# smc.net
KiCad netlist of a schematic drawn in EAGLE
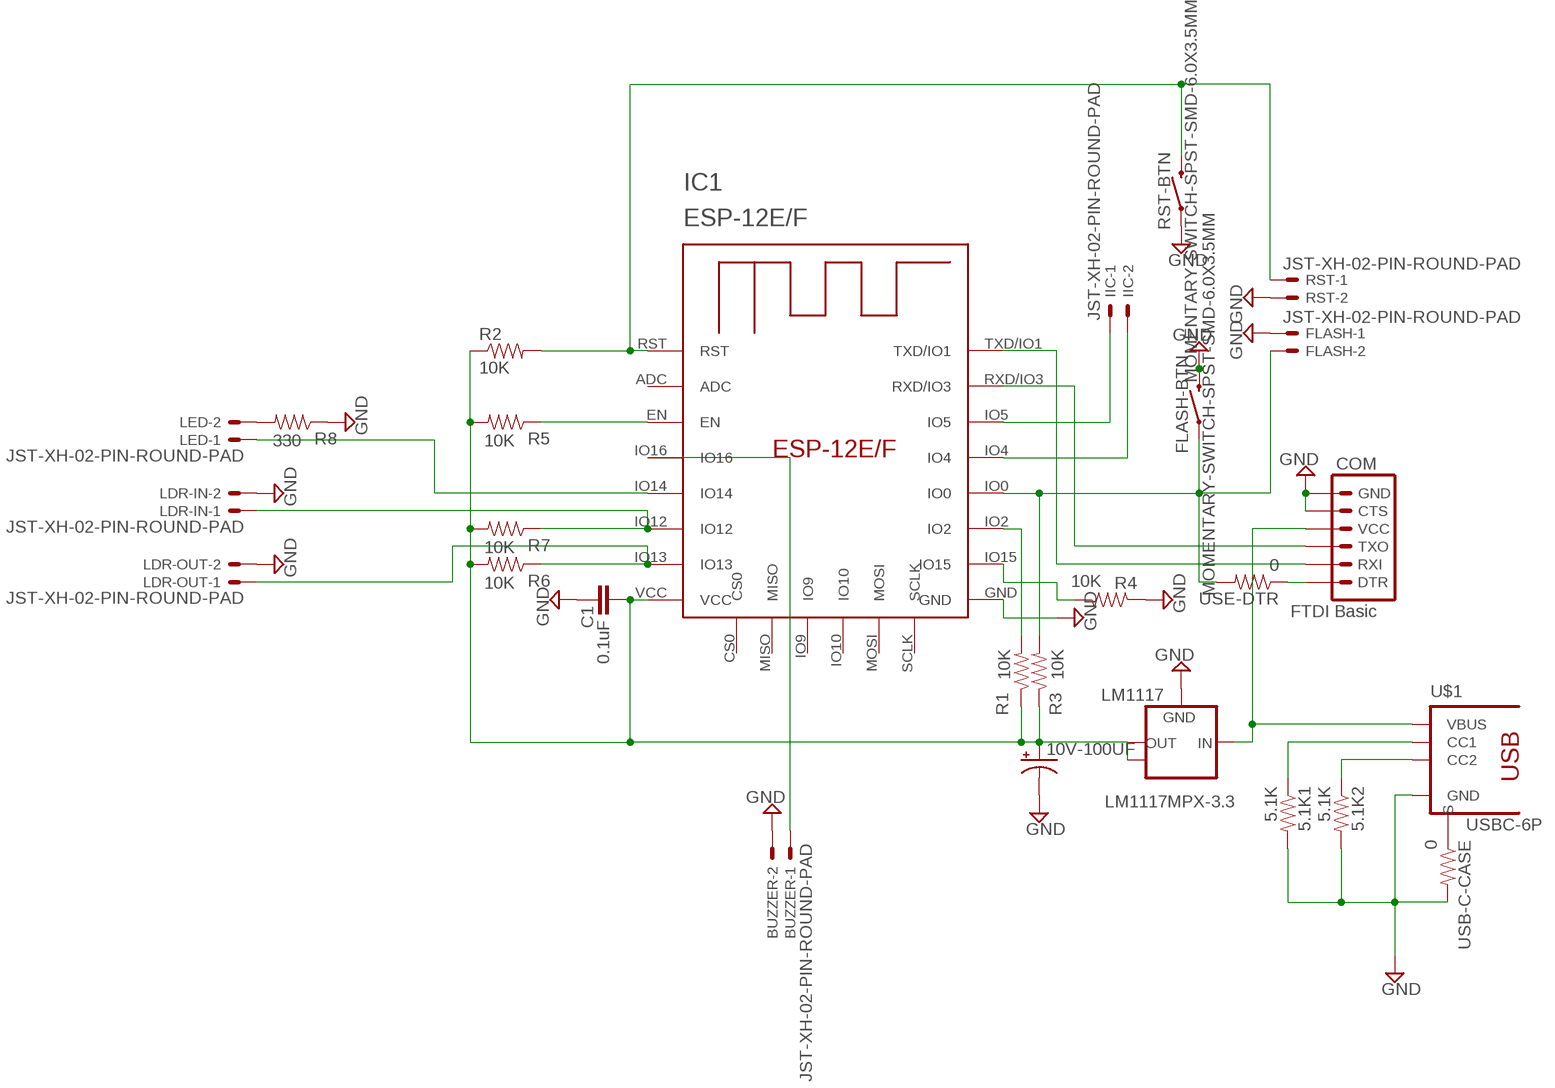
[diagram p0: schematic, sheet 1]

(export (version "E")
  (design (tool "Eeschema 10.0.6"))
  (components
    (comp (ref "5.1K1")
      (value "5.1K")
      (footprint "eagle-import:0603-RES")
      (libsource (lib "eagle-import") (part "RESISTOR0603-RES"))
    )
    (comp (ref "5.1K2")
      (value "5.1K")
      (footprint "eagle-import:0603-RES")
      (libsource (lib "eagle-import") (part "RESISTOR0603-RES"))
    )
    (comp (ref "10V-100UF")
      (value "CPOL-USA/3216-18W")
      (footprint "eagle-import:A_3216-18W")
      (libsource (lib "eagle-import") (part "CPOL-USA/3216-18W"))
    )
    (comp (ref "BUZZER")
      (value "JST-XH-02-PIN-ROUND-PAD")
      (footprint "eagle-import:JST-XH-02-PACKAGE-ROUND-PAD")
      (libsource (lib "eagle-import") (part "JST-XH-02-PIN-ROUND-PAD"))
    )
    (comp (ref "C1")
      (value "0.1uF")
      (footprint "eagle-import:0603-CAP")
      (libsource (lib "eagle-import") (part "CAP0603-CAP"))
    )
    (comp (ref "COM")
      (value "FTDI Basic")
      (footprint "eagle-import:1X06")
      (libsource (lib "eagle-import") (part "ARDUINO_SERIAL_PROGRAMPTH"))
    )
    (comp (ref "FLASH")
      (value "JST-XH-02-PIN-ROUND-PAD")
      (footprint "eagle-import:JST-XH-02-PACKAGE-ROUND-PAD")
      (libsource (lib "eagle-import") (part "JST-XH-02-PIN-ROUND-PAD"))
    )
    (comp (ref "FLASH-BTN")
      (value "MOMENTARY-SWITCH-SPST-SMD-6.0X3.5MM")
      (footprint "eagle-import:TACTILE_SWITCH_SMD_6.0X3.5MM")
      (libsource (lib "eagle-import") (part "MOMENTARY-SWITCH-SPST-SMD-6.0X3.5MM"))
    )
    (comp (ref "IC1")
      (value "ESP-12E/F")
      (footprint "eagle-import:ESP-12E")
      (libsource (lib "eagle-import") (part "ESP-12E/F"))
    )
    (comp (ref "IIC")
      (value "JST-XH-02-PIN-ROUND-PAD")
      (footprint "eagle-import:JST-XH-02-PACKAGE-ROUND-PAD")
      (libsource (lib "eagle-import") (part "JST-XH-02-PIN-ROUND-PAD"))
    )
    (comp (ref "LDR-IN")
      (value "JST-XH-02-PIN-ROUND-PAD")
      (footprint "eagle-import:JST-XH-02-PACKAGE-ROUND-PAD")
      (libsource (lib "eagle-import") (part "JST-XH-02-PIN-ROUND-PAD"))
    )
    (comp (ref "LDR-OUT")
      (value "JST-XH-02-PIN-ROUND-PAD")
      (footprint "eagle-import:JST-XH-02-PACKAGE-ROUND-PAD")
      (libsource (lib "eagle-import") (part "JST-XH-02-PIN-ROUND-PAD"))
    )
    (comp (ref "LED")
      (value "JST-XH-02-PIN-ROUND-PAD")
      (footprint "eagle-import:JST-XH-02-PACKAGE-ROUND-PAD")
      (libsource (lib "eagle-import") (part "JST-XH-02-PIN-ROUND-PAD"))
    )
    (comp (ref "LM1117")
      (value "LM1117MPX-3.3")
      (footprint "eagle-import:SOT223")
      (libsource (lib "eagle-import") (part "LM1117MPX-3.3"))
    )
    (comp (ref "R1")
      (value "10K")
      (footprint "eagle-import:0603-RES")
      (libsource (lib "eagle-import") (part "RESISTOR0603-RES"))
    )
    (comp (ref "R2")
      (value "10K")
      (footprint "eagle-import:0603-RES")
      (libsource (lib "eagle-import") (part "RESISTOR0603-RES"))
    )
    (comp (ref "R3")
      (value "10K")
      (footprint "eagle-import:0603-RES")
      (libsource (lib "eagle-import") (part "RESISTOR0603-RES"))
    )
    (comp (ref "R4")
      (value "10K")
      (footprint "eagle-import:0603-RES")
      (libsource (lib "eagle-import") (part "RESISTOR0603-RES"))
    )
    (comp (ref "R5")
      (value "10K")
      (footprint "eagle-import:0603-RES")
      (libsource (lib "eagle-import") (part "RESISTOR0603-RES"))
    )
    (comp (ref "R6")
      (value "10K")
      (footprint "eagle-import:0603-RES")
      (libsource (lib "eagle-import") (part "RESISTOR0603-RES"))
    )
    (comp (ref "R7")
      (value "10K")
      (footprint "eagle-import:0603-RES")
      (libsource (lib "eagle-import") (part "RESISTOR0603-RES"))
    )
    (comp (ref "R8")
      (value "330")
      (footprint "eagle-import:0603-RES")
      (libsource (lib "eagle-import") (part "RESISTOR0603-RES"))
    )
    (comp (ref "RST")
      (value "JST-XH-02-PIN-ROUND-PAD")
      (footprint "eagle-import:JST-XH-02-PACKAGE-ROUND-PAD")
      (libsource (lib "eagle-import") (part "JST-XH-02-PIN-ROUND-PAD"))
    )
    (comp (ref "RST-BTN")
      (value "MOMENTARY-SWITCH-SPST-SMD-6.0X3.5MM")
      (footprint "eagle-import:TACTILE_SWITCH_SMD_6.0X3.5MM")
      (libsource (lib "eagle-import") (part "MOMENTARY-SWITCH-SPST-SMD-6.0X3.5MM"))
    )
    (comp (ref "U$1")
      (value "USBC-6P")
      (footprint "eagle-import:USCX-06FX-XXMX-01")
      (libsource (lib "eagle-import") (part "USBC-6P"))
    )
    (comp (ref "USB-C-CASE")
      (value "0")
      (footprint "eagle-import:0603-RES")
      (libsource (lib "eagle-import") (part "RESISTOR0603-RES"))
    )
    (comp (ref "USE-DTR")
      (value "0")
      (footprint "eagle-import:0603-RES")
      (libsource (lib "eagle-import") (part "RESISTOR0603-RES"))
    )
  )
  (nets
    (net (code "1") (name "GND") (class "Default")
      (node (ref "10V-100UF") (pin "-") (pinfunction "-_-") (pintype "passive"))
      (node (ref "5.1K1") (pin "2") (pinfunction "2_2") (pintype "passive"))
      (node (ref "5.1K2") (pin "2") (pinfunction "2_2") (pintype "passive"))
      (node (ref "BUZZER") (pin "2") (pinfunction "S_2") (pintype "passive"))
      (node (ref "C1") (pin "2") (pinfunction "2_2") (pintype "passive"))
      (node (ref "COM") (pin "5") (pinfunction "CTS_5") (pintype "passive"))
      (node (ref "COM") (pin "6") (pinfunction "GND_6") (pintype "passive"))
      (node (ref "FLASH") (pin "1") (pinfunction "S_1") (pintype "passive"))
      (node (ref "FLASH-BTN") (pin "2") (pinfunction "2_2") (pintype "passive"))
      (node (ref "IC1") (pin "GND") (pinfunction "GND_GND") (pintype "power_in"))
      (node (ref "LDR-IN") (pin "2") (pinfunction "S_2") (pintype "passive"))
      (node (ref "LDR-OUT") (pin "2") (pinfunction "S_2") (pintype "passive"))
      (node (ref "LM1117") (pin "1") (pinfunction "GND_1") (pintype "input"))
      (node (ref "R4") (pin "1") (pinfunction "1_1") (pintype "passive"))
      (node (ref "R8") (pin "1") (pinfunction "1_1") (pintype "passive"))
      (node (ref "RST") (pin "2") (pinfunction "S_2") (pintype "passive"))
      (node (ref "RST-BTN") (pin "1") (pinfunction "1_1") (pintype "passive"))
      (node (ref "U$1") (pin "GND1") (pinfunction "GND_GND1") (pintype "power_in"))
      (node (ref "U$1") (pin "GND2") (pinfunction "GND_GND2") (pintype "power_in"))
      (node (ref "USB-C-CASE") (pin "2") (pinfunction "2_2") (pintype "passive"))
    )
    (net (code "2") (name "Net-(5.1K1-Pad1)") (class "Default")
      (node (ref "5.1K1") (pin "1") (pinfunction "1_1") (pintype "passive"))
      (node (ref "U$1") (pin "CC1") (pinfunction "CC1_CC1") (pintype "bidirectional"))
    )
    (net (code "3") (name "Net-(5.1K2-Pad1)") (class "Default")
      (node (ref "5.1K2") (pin "1") (pinfunction "1_1") (pintype "passive"))
      (node (ref "U$1") (pin "CC2") (pinfunction "CC2_CC2") (pintype "bidirectional"))
    )
    (net (code "4") (name "Net-(BUZZERA-S)") (class "Default")
      (node (ref "BUZZER") (pin "1") (pinfunction "S_1") (pintype "passive"))
      (node (ref "IC1") (pin "IO16") (pinfunction "IO16_IO16") (pintype "bidirectional"))
    )
    (net (code "5") (name "Net-(COM-DTR)") (class "Default")
      (node (ref "COM") (pin "1") (pinfunction "DTR_1") (pintype "passive"))
      (node (ref "USE-DTR") (pin "1") (pinfunction "1_1") (pintype "passive"))
    )
    (net (code "6") (name "Net-(COM-RXI)") (class "Default")
      (node (ref "COM") (pin "2") (pinfunction "RXI_2") (pintype "passive"))
      (node (ref "IC1") (pin "TXD/IO1") (pinfunction "TXD/IO1_TXD/IO1") (pintype "bidirectional"))
    )
    (net (code "7") (name "Net-(COM-TXO)") (class "Default")
      (node (ref "COM") (pin "3") (pinfunction "TXO_3") (pintype "passive"))
      (node (ref "IC1") (pin "RXD/IO3") (pinfunction "RXD/IO3_RXD/IO3") (pintype "bidirectional"))
    )
    (net (code "8") (name "Net-(COM-VCC)") (class "Default")
      (node (ref "COM") (pin "4") (pinfunction "VCC_4") (pintype "passive"))
      (node (ref "LM1117") (pin "3") (pinfunction "IN_3") (pintype "input"))
      (node (ref "U$1") (pin "VBUS1") (pinfunction "VBUS_VBUS1") (pintype "power_in"))
      (node (ref "U$1") (pin "VBUS2") (pinfunction "VBUS_VBUS2") (pintype "power_in"))
    )
    (net (code "9") (name "Net-(FLASHB-S)") (class "Default")
      (node (ref "FLASH") (pin "2") (pinfunction "S_2") (pintype "passive"))
      (node (ref "FLASH-BTN") (pin "1") (pinfunction "1_1") (pintype "passive"))
      (node (ref "IC1") (pin "IO0") (pinfunction "IO0_IO0") (pintype "bidirectional"))
      (node (ref "R3") (pin "2") (pinfunction "2_2") (pintype "passive"))
      (node (ref "USE-DTR") (pin "2") (pinfunction "2_2") (pintype "passive"))
    )
    (net (code "10") (name "Net-(IC1-PadEN)") (class "Default")
      (node (ref "IC1") (pin "EN") (pinfunction "EN_EN") (pintype "bidirectional"))
      (node (ref "R5") (pin "1") (pinfunction "1_1") (pintype "passive"))
    )
    (net (code "11") (name "Net-(IC1-PadIO2)") (class "Default")
      (node (ref "IC1") (pin "IO2") (pinfunction "IO2_IO2") (pintype "bidirectional"))
      (node (ref "R1") (pin "2") (pinfunction "2_2") (pintype "passive"))
    )
    (net (code "12") (name "Net-(IC1-PadIO15)") (class "Default")
      (node (ref "IC1") (pin "IO15") (pinfunction "IO15_IO15") (pintype "bidirectional"))
      (node (ref "R4") (pin "2") (pinfunction "2_2") (pintype "passive"))
    )
    (net (code "13") (name "Net-(IICA-S)") (class "Default")
      (node (ref "IC1") (pin "IO5") (pinfunction "IO5_IO5") (pintype "bidirectional"))
      (node (ref "IIC") (pin "1") (pinfunction "S_1") (pintype "passive"))
    )
    (net (code "14") (name "Net-(IICB-S)") (class "Default")
      (node (ref "IC1") (pin "IO4") (pinfunction "IO4_IO4") (pintype "bidirectional"))
      (node (ref "IIC") (pin "2") (pinfunction "S_2") (pintype "passive"))
    )
    (net (code "15") (name "Net-(LDR-INA-S)") (class "Default")
      (node (ref "IC1") (pin "IO12") (pinfunction "IO12_IO12") (pintype "bidirectional"))
      (node (ref "LDR-IN") (pin "1") (pinfunction "S_1") (pintype "passive"))
      (node (ref "R7") (pin "1") (pinfunction "1_1") (pintype "passive"))
    )
    (net (code "16") (name "Net-(LDR-OUTA-S)") (class "Default")
      (node (ref "IC1") (pin "IO13") (pinfunction "IO13_IO13") (pintype "bidirectional"))
      (node (ref "LDR-OUT") (pin "1") (pinfunction "S_1") (pintype "passive"))
      (node (ref "R6") (pin "1") (pinfunction "1_1") (pintype "passive"))
    )
    (net (code "17") (name "Net-(LEDA-S)") (class "Default")
      (node (ref "IC1") (pin "IO14") (pinfunction "IO14_IO14") (pintype "bidirectional"))
      (node (ref "LED") (pin "1") (pinfunction "S_1") (pintype "passive"))
    )
    (net (code "18") (name "Net-(LEDB-S)") (class "Default")
      (node (ref "LED") (pin "2") (pinfunction "S_2") (pintype "passive"))
      (node (ref "R8") (pin "2") (pinfunction "2_2") (pintype "passive"))
    )
    (net (code "19") (name "Net-(LM1117-OUT)") (class "Default")
      (node (ref "10V-100UF") (pin "+") (pinfunction "+_+") (pintype "passive"))
      (node (ref "C1") (pin "1") (pinfunction "1_1") (pintype "passive"))
      (node (ref "IC1") (pin "VCC") (pinfunction "VCC_VCC") (pintype "power_in"))
      (node (ref "LM1117") (pin "2") (pinfunction "OUT_2") (pintype "passive"))
      (node (ref "LM1117") (pin "TAB") (pinfunction "OUT1_TAB") (pintype "passive"))
      (node (ref "R1") (pin "1") (pinfunction "1_1") (pintype "passive"))
      (node (ref "R2") (pin "1") (pinfunction "1_1") (pintype "passive"))
      (node (ref "R3") (pin "1") (pinfunction "1_1") (pintype "passive"))
      (node (ref "R5") (pin "2") (pinfunction "2_2") (pintype "passive"))
      (node (ref "R6") (pin "2") (pinfunction "2_2") (pintype "passive"))
      (node (ref "R7") (pin "2") (pinfunction "2_2") (pintype "passive"))
    )
    (net (code "20") (name "Net-(RSTA-S)") (class "Default")
      (node (ref "IC1") (pin "RST") (pinfunction "RST_RST") (pintype "input"))
      (node (ref "R2") (pin "2") (pinfunction "2_2") (pintype "passive"))
      (node (ref "RST") (pin "1") (pinfunction "S_1") (pintype "passive"))
      (node (ref "RST-BTN") (pin "2") (pinfunction "2_2") (pintype "passive"))
    )
    (net (code "21") (name "Net-(U$1-S-PadSHIELD1)") (class "Default")
      (node (ref "U$1") (pin "SHIELD1") (pinfunction "S_SHIELD1") (pintype "passive"))
      (node (ref "U$1") (pin "SHIELD2") (pinfunction "S_SHIELD2") (pintype "passive"))
      (node (ref "U$1") (pin "SHIELD3") (pinfunction "S_SHIELD3") (pintype "passive"))
      (node (ref "U$1") (pin "SHIELD4") (pinfunction "S_SHIELD4") (pintype "passive"))
      (node (ref "USB-C-CASE") (pin "1") (pinfunction "1_1") (pintype "passive"))
    )
    (net (code "22") (name "unconnected-(IC1-PadADC)") (class "Default")
      (node (ref "IC1") (pin "ADC") (pinfunction "ADC_ADC") (pintype "bidirectional"))
    )
    (net (code "23") (name "unconnected-(IC1-PadCS0)") (class "Default")
      (node (ref "IC1") (pin "CS0") (pinfunction "CS0_CS0") (pintype "bidirectional"))
    )
    (net (code "24") (name "unconnected-(IC1-PadIO9)") (class "Default")
      (node (ref "IC1") (pin "IO9") (pinfunction "IO9_IO9") (pintype "bidirectional"))
    )
    (net (code "25") (name "unconnected-(IC1-PadIO10)") (class "Default")
      (node (ref "IC1") (pin "IO10") (pinfunction "IO10_IO10") (pintype "bidirectional"))
    )
    (net (code "26") (name "unconnected-(IC1-PadMISO)") (class "Default")
      (node (ref "IC1") (pin "MISO") (pinfunction "MISO_MISO") (pintype "bidirectional"))
    )
    (net (code "27") (name "unconnected-(IC1-PadMOSI)") (class "Default")
      (node (ref "IC1") (pin "MOSI") (pinfunction "MOSI_MOSI") (pintype "bidirectional"))
    )
    (net (code "28") (name "unconnected-(IC1-PadSCLK)") (class "Default")
      (node (ref "IC1") (pin "SCLK") (pinfunction "SCLK_SCLK") (pintype "bidirectional"))
    )
  )
)
